# Main.net
KiCad netlist of a schematic drawn in EAGLE
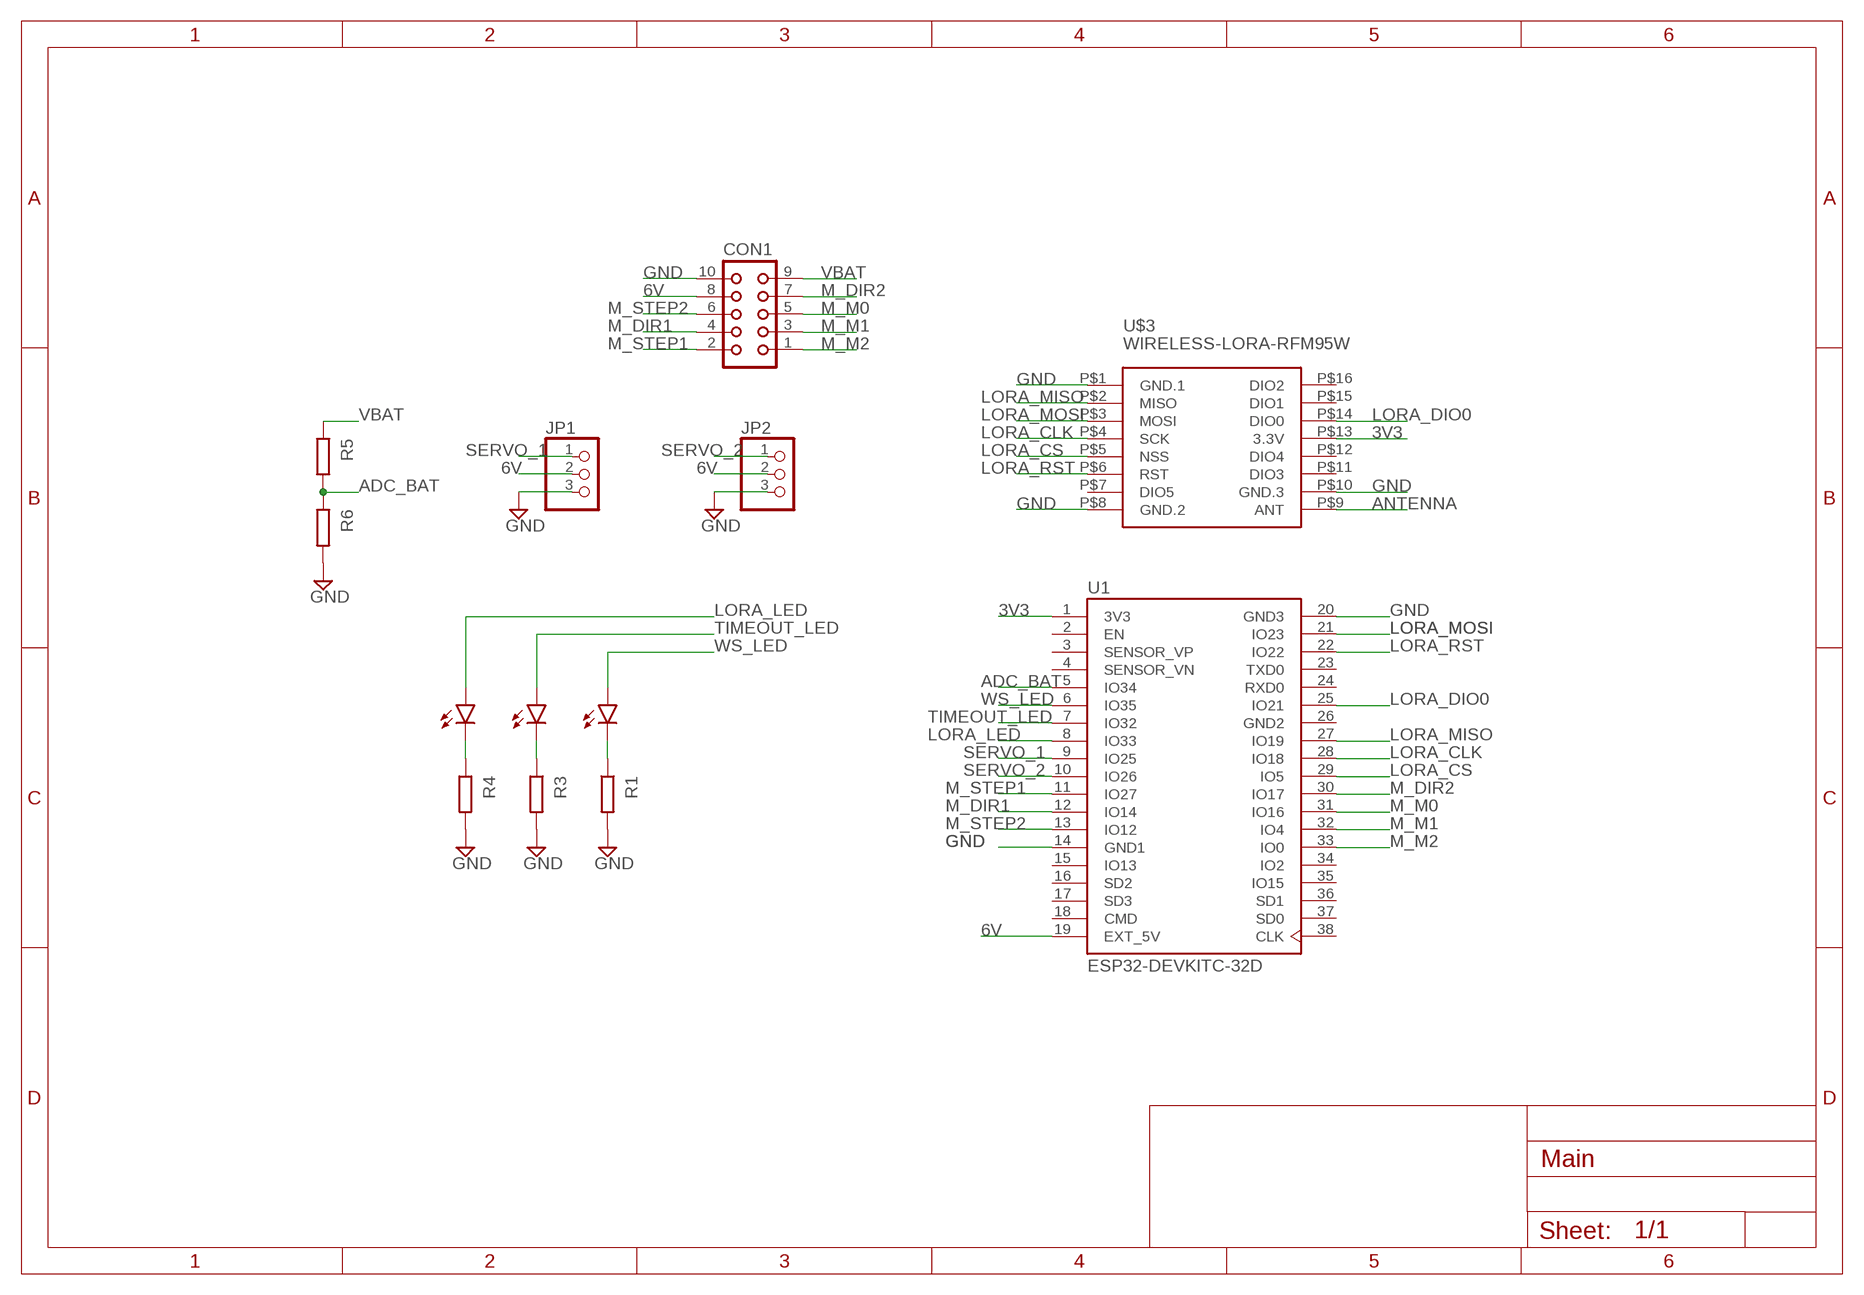
[diagram p0: schematic, sheet 1]

(export (version "E")
  (design (tool "Eeschema 10.0.6"))
  (components
    (comp (ref "CON1")
      (value "CON10")
      (footprint "eagle-import:CON10")
      (libsource (lib "eagle-import") (part "CON10"))
    )
    (comp (ref "JP1")
      (value "PINHD-1X3")
      (footprint "eagle-import:1X03")
      (libsource (lib "eagle-import") (part "PINHD-1X3"))
    )
    (comp (ref "JP2")
      (value "PINHD-1X3")
      (footprint "eagle-import:1X03")
      (libsource (lib "eagle-import") (part "PINHD-1X3"))
    )
    (comp (ref "LORA")
      (value "LED_BLUE")
      (footprint "eagle-import:LEDRD254W60D565H860B_B")
      (libsource (lib "eagle-import") (part "LEDBLUE_"))
    )
    (comp (ref "MV")
      (value "LED_BLUE")
      (footprint "eagle-import:LEDRD254W60D565H860B_B")
      (libsource (lib "eagle-import") (part "LEDBLUE_"))
    )
    (comp (ref "R1")
      (value "R_CHIP-0603(1608-METRIC)")
      (footprint "eagle-import:RESC1608X60")
      (libsource (lib "eagle-import") (part "RCHIP-0603(1608-METRIC)_"))
    )
    (comp (ref "R3")
      (value "R_CHIP-0603(1608-METRIC)")
      (footprint "eagle-import:RESC1608X60")
      (libsource (lib "eagle-import") (part "RCHIP-0603(1608-METRIC)_"))
    )
    (comp (ref "R4")
      (value "R_CHIP-0603(1608-METRIC)")
      (footprint "eagle-import:RESC1608X60")
      (libsource (lib "eagle-import") (part "RCHIP-0603(1608-METRIC)_"))
    )
    (comp (ref "R5")
      (value "R_CHIP-0603(1608-METRIC)")
      (footprint "eagle-import:RESC1608X60")
      (libsource (lib "eagle-import") (part "RCHIP-0603(1608-METRIC)_"))
    )
    (comp (ref "R6")
      (value "R_CHIP-0603(1608-METRIC)")
      (footprint "eagle-import:RESC1608X60")
      (libsource (lib "eagle-import") (part "RCHIP-0603(1608-METRIC)_"))
    )
    (comp (ref "TOUT")
      (value "LED_BLUE")
      (footprint "eagle-import:LEDRD254W60D565H860B_B")
      (libsource (lib "eagle-import") (part "LEDBLUE_"))
    )
    (comp (ref "U$3")
      (value "WIRELESS-LORA-RFM95W")
      (footprint "eagle-import:LORA-BREAKOUT")
      (libsource (lib "eagle-import") (part "WIRELESS-LORA-RFM95W"))
    )
    (comp (ref "U1")
      (value "ESP32-DEVKITC-32D")
      (footprint "eagle-import:MODULE_ESP32-DEVKITC-32D")
      (fields (field (name "MF") "Espressif Systems"))
      (libsource (lib "eagle-import") (part "ESP32-DEVKITC-32D"))
    )
  )
  (nets
    (net (code "1") (name "/3V3") (class "Default")
      (node (ref "U$3") (pin "P$13") (pinfunction "3.3V_P$13") (pintype "power_in"))
      (node (ref "U1") (pin "1") (pinfunction "3V3_1") (pintype "power_in"))
    )
    (net (code "2") (name "/6V") (class "Default")
      (node (ref "CON1") (pin "8") (pinfunction "8_8") (pintype "passive"))
      (node (ref "JP1") (pin "2") (pinfunction "2_2") (pintype "passive"))
      (node (ref "JP2") (pin "2") (pinfunction "2_2") (pintype "passive"))
      (node (ref "U1") (pin "19") (pinfunction "EXT_5V_19") (pintype "power_in"))
    )
    (net (code "3") (name "/ADC_BAT") (class "Default")
      (node (ref "R5") (pin "2") (pinfunction "2_2") (pintype "passive"))
      (node (ref "R6") (pin "1") (pinfunction "1_1") (pintype "passive"))
      (node (ref "U1") (pin "5") (pinfunction "IO34_5") (pintype "bidirectional"))
    )
    (net (code "4") (name "/ANTENNA") (class "Default")
      (node (ref "U$3") (pin "P$9") (pinfunction "ANT_P$9") (pintype "passive"))
    )
    (net (code "5") (name "/GND2") (class "Default")
      (node (ref "U1") (pin "26") (pinfunction "GND2_26") (pintype "power_in"))
    )
    (net (code "6") (name "/LORA_CLK") (class "Default")
      (node (ref "U$3") (pin "P$4") (pinfunction "SCK_P$4") (pintype "bidirectional"))
      (node (ref "U1") (pin "28") (pinfunction "IO18_28") (pintype "bidirectional"))
    )
    (net (code "7") (name "/LORA_CS") (class "Default")
      (node (ref "U$3") (pin "P$5") (pinfunction "NSS_P$5") (pintype "bidirectional"))
      (node (ref "U1") (pin "29") (pinfunction "IO5_29") (pintype "bidirectional"))
    )
    (net (code "8") (name "/LORA_DIO0") (class "Default")
      (node (ref "U$3") (pin "P$14") (pinfunction "DIO0_P$14") (pintype "bidirectional"))
      (node (ref "U1") (pin "25") (pinfunction "IO21_25") (pintype "bidirectional"))
    )
    (net (code "9") (name "/LORA_LED") (class "Default")
      (node (ref "MV") (pin "1") (pinfunction "A_1") (pintype "passive"))
      (node (ref "U1") (pin "8") (pinfunction "IO33_8") (pintype "bidirectional"))
    )
    (net (code "10") (name "/LORA_MISO") (class "Default")
      (node (ref "U$3") (pin "P$2") (pinfunction "MISO_P$2") (pintype "bidirectional"))
      (node (ref "U1") (pin "27") (pinfunction "IO19_27") (pintype "bidirectional"))
    )
    (net (code "11") (name "/LORA_MOSI") (class "Default")
      (node (ref "U$3") (pin "P$3") (pinfunction "MOSI_P$3") (pintype "bidirectional"))
      (node (ref "U1") (pin "21") (pinfunction "IO23_21") (pintype "bidirectional"))
    )
    (net (code "12") (name "/LORA_RST") (class "Default")
      (node (ref "U$3") (pin "P$6") (pinfunction "RST_P$6") (pintype "bidirectional"))
      (node (ref "U1") (pin "22") (pinfunction "IO22_22") (pintype "bidirectional"))
    )
    (net (code "13") (name "/M_DIR1") (class "Default")
      (node (ref "CON1") (pin "4") (pinfunction "4_4") (pintype "passive"))
      (node (ref "U1") (pin "12") (pinfunction "IO14_12") (pintype "bidirectional"))
    )
    (net (code "14") (name "/M_DIR2") (class "Default")
      (node (ref "CON1") (pin "7") (pinfunction "7_7") (pintype "passive"))
      (node (ref "U1") (pin "30") (pinfunction "IO17_30") (pintype "bidirectional"))
    )
    (net (code "15") (name "/M_M0") (class "Default")
      (node (ref "CON1") (pin "5") (pinfunction "5_5") (pintype "passive"))
      (node (ref "U1") (pin "31") (pinfunction "IO16_31") (pintype "bidirectional"))
    )
    (net (code "16") (name "/M_M1") (class "Default")
      (node (ref "CON1") (pin "3") (pinfunction "3_3") (pintype "passive"))
      (node (ref "U1") (pin "32") (pinfunction "IO4_32") (pintype "bidirectional"))
    )
    (net (code "17") (name "/M_M2") (class "Default")
      (node (ref "CON1") (pin "1") (pinfunction "1_1") (pintype "passive"))
      (node (ref "U1") (pin "33") (pinfunction "IO0_33") (pintype "bidirectional"))
    )
    (net (code "18") (name "/M_STEP1") (class "Default")
      (node (ref "CON1") (pin "2") (pinfunction "2_2") (pintype "passive"))
      (node (ref "U1") (pin "11") (pinfunction "IO27_11") (pintype "bidirectional"))
    )
    (net (code "19") (name "/M_STEP2") (class "Default")
      (node (ref "CON1") (pin "6") (pinfunction "6_6") (pintype "passive"))
      (node (ref "U1") (pin "13") (pinfunction "IO12_13") (pintype "bidirectional"))
    )
    (net (code "20") (name "/SERVO_1") (class "Default")
      (node (ref "JP1") (pin "1") (pinfunction "1_1") (pintype "passive"))
      (node (ref "U1") (pin "9") (pinfunction "IO25_9") (pintype "bidirectional"))
    )
    (net (code "21") (name "/SERVO_2") (class "Default")
      (node (ref "JP2") (pin "1") (pinfunction "1_1") (pintype "passive"))
      (node (ref "U1") (pin "10") (pinfunction "IO26_10") (pintype "bidirectional"))
    )
    (net (code "22") (name "/TIMEOUT_LED") (class "Default")
      (node (ref "TOUT") (pin "1") (pinfunction "A_1") (pintype "passive"))
      (node (ref "U1") (pin "7") (pinfunction "IO32_7") (pintype "bidirectional"))
    )
    (net (code "23") (name "/VBAT") (class "Default")
      (node (ref "CON1") (pin "9") (pinfunction "9_9") (pintype "passive"))
      (node (ref "R5") (pin "1") (pinfunction "1_1") (pintype "passive"))
    )
    (net (code "24") (name "/WS_LED") (class "Default")
      (node (ref "LORA") (pin "1") (pinfunction "A_1") (pintype "passive"))
      (node (ref "U1") (pin "6") (pinfunction "IO35_6") (pintype "bidirectional"))
    )
    (net (code "25") (name "GND") (class "Default")
      (node (ref "CON1") (pin "10") (pinfunction "10_10") (pintype "passive"))
      (node (ref "JP1") (pin "3") (pinfunction "3_3") (pintype "passive"))
      (node (ref "JP2") (pin "3") (pinfunction "3_3") (pintype "passive"))
      (node (ref "R1") (pin "2") (pinfunction "2_2") (pintype "passive"))
      (node (ref "R3") (pin "2") (pinfunction "2_2") (pintype "passive"))
      (node (ref "R4") (pin "2") (pinfunction "2_2") (pintype "passive"))
      (node (ref "R6") (pin "2") (pinfunction "2_2") (pintype "passive"))
      (node (ref "U$3") (pin "P$1") (pinfunction "GND.1_P$1") (pintype "power_in"))
      (node (ref "U$3") (pin "P$10") (pinfunction "GND.3_P$10") (pintype "power_in"))
      (node (ref "U$3") (pin "P$8") (pinfunction "GND.2_P$8") (pintype "power_in"))
      (node (ref "U1") (pin "14") (pinfunction "GND1_14") (pintype "power_in"))
      (node (ref "U1") (pin "20") (pinfunction "GND3_20") (pintype "power_in"))
    )
    (net (code "26") (name "Net-(LORA-C)") (class "Default")
      (node (ref "LORA") (pin "2") (pinfunction "C_2") (pintype "passive"))
      (node (ref "R1") (pin "1") (pinfunction "1_1") (pintype "passive"))
    )
    (net (code "27") (name "Net-(MV-C)") (class "Default")
      (node (ref "MV") (pin "2") (pinfunction "C_2") (pintype "passive"))
      (node (ref "R4") (pin "1") (pinfunction "1_1") (pintype "passive"))
    )
    (net (code "28") (name "Net-(TOUT-C)") (class "Default")
      (node (ref "R3") (pin "1") (pinfunction "1_1") (pintype "passive"))
      (node (ref "TOUT") (pin "2") (pinfunction "C_2") (pintype "passive"))
    )
    (net (code "29") (name "unconnected-(U$3-DIO1-PadP$15)") (class "Default")
      (node (ref "U$3") (pin "P$15") (pinfunction "DIO1_P$15") (pintype "bidirectional"))
    )
    (net (code "30") (name "unconnected-(U$3-DIO2-PadP$16)") (class "Default")
      (node (ref "U$3") (pin "P$16") (pinfunction "DIO2_P$16") (pintype "bidirectional"))
    )
    (net (code "31") (name "unconnected-(U$3-DIO3-PadP$11)") (class "Default")
      (node (ref "U$3") (pin "P$11") (pinfunction "DIO3_P$11") (pintype "bidirectional"))
    )
    (net (code "32") (name "unconnected-(U$3-DIO4-PadP$12)") (class "Default")
      (node (ref "U$3") (pin "P$12") (pinfunction "DIO4_P$12") (pintype "bidirectional"))
    )
    (net (code "33") (name "unconnected-(U$3-DIO5-PadP$7)") (class "Default")
      (node (ref "U$3") (pin "P$7") (pinfunction "DIO5_P$7") (pintype "bidirectional"))
    )
    (net (code "34") (name "unconnected-(U1-CLK-Pad38)") (class "Default")
      (node (ref "U1") (pin "38") (pinfunction "CLK_38") (pintype "input"))
    )
    (net (code "35") (name "unconnected-(U1-CMD-Pad18)") (class "Default")
      (node (ref "U1") (pin "18") (pinfunction "CMD_18") (pintype "bidirectional"))
    )
    (net (code "36") (name "unconnected-(U1-EN-Pad2)") (class "Default")
      (node (ref "U1") (pin "2") (pinfunction "EN_2") (pintype "input"))
    )
    (net (code "37") (name "unconnected-(U1-IO2-Pad34)") (class "Default")
      (node (ref "U1") (pin "34") (pinfunction "IO2_34") (pintype "bidirectional"))
    )
    (net (code "38") (name "unconnected-(U1-IO13-Pad15)") (class "Default")
      (node (ref "U1") (pin "15") (pinfunction "IO13_15") (pintype "bidirectional"))
    )
    (net (code "39") (name "unconnected-(U1-IO15-Pad35)") (class "Default")
      (node (ref "U1") (pin "35") (pinfunction "IO15_35") (pintype "bidirectional"))
    )
    (net (code "40") (name "unconnected-(U1-RXD0-Pad24)") (class "Default")
      (node (ref "U1") (pin "24") (pinfunction "RXD0_24") (pintype "input"))
    )
    (net (code "41") (name "unconnected-(U1-SD0-Pad37)") (class "Default")
      (node (ref "U1") (pin "37") (pinfunction "SD0_37") (pintype "bidirectional"))
    )
    (net (code "42") (name "unconnected-(U1-SD1-Pad36)") (class "Default")
      (node (ref "U1") (pin "36") (pinfunction "SD1_36") (pintype "bidirectional"))
    )
    (net (code "43") (name "unconnected-(U1-SD2-Pad16)") (class "Default")
      (node (ref "U1") (pin "16") (pinfunction "SD2_16") (pintype "bidirectional"))
    )
    (net (code "44") (name "unconnected-(U1-SD3-Pad17)") (class "Default")
      (node (ref "U1") (pin "17") (pinfunction "SD3_17") (pintype "bidirectional"))
    )
    (net (code "45") (name "unconnected-(U1-SENSOR_VN-Pad4)") (class "Default")
      (node (ref "U1") (pin "4") (pinfunction "SENSOR_VN_4") (pintype "input"))
    )
    (net (code "46") (name "unconnected-(U1-SENSOR_VP-Pad3)") (class "Default")
      (node (ref "U1") (pin "3") (pinfunction "SENSOR_VP_3") (pintype "input"))
    )
    (net (code "47") (name "unconnected-(U1-TXD0-Pad23)") (class "Default")
      (node (ref "U1") (pin "23") (pinfunction "TXD0_23") (pintype "output"))
    )
  )
)
